# avr-clock.net
KiCad netlist of a schematic drawn in EAGLE
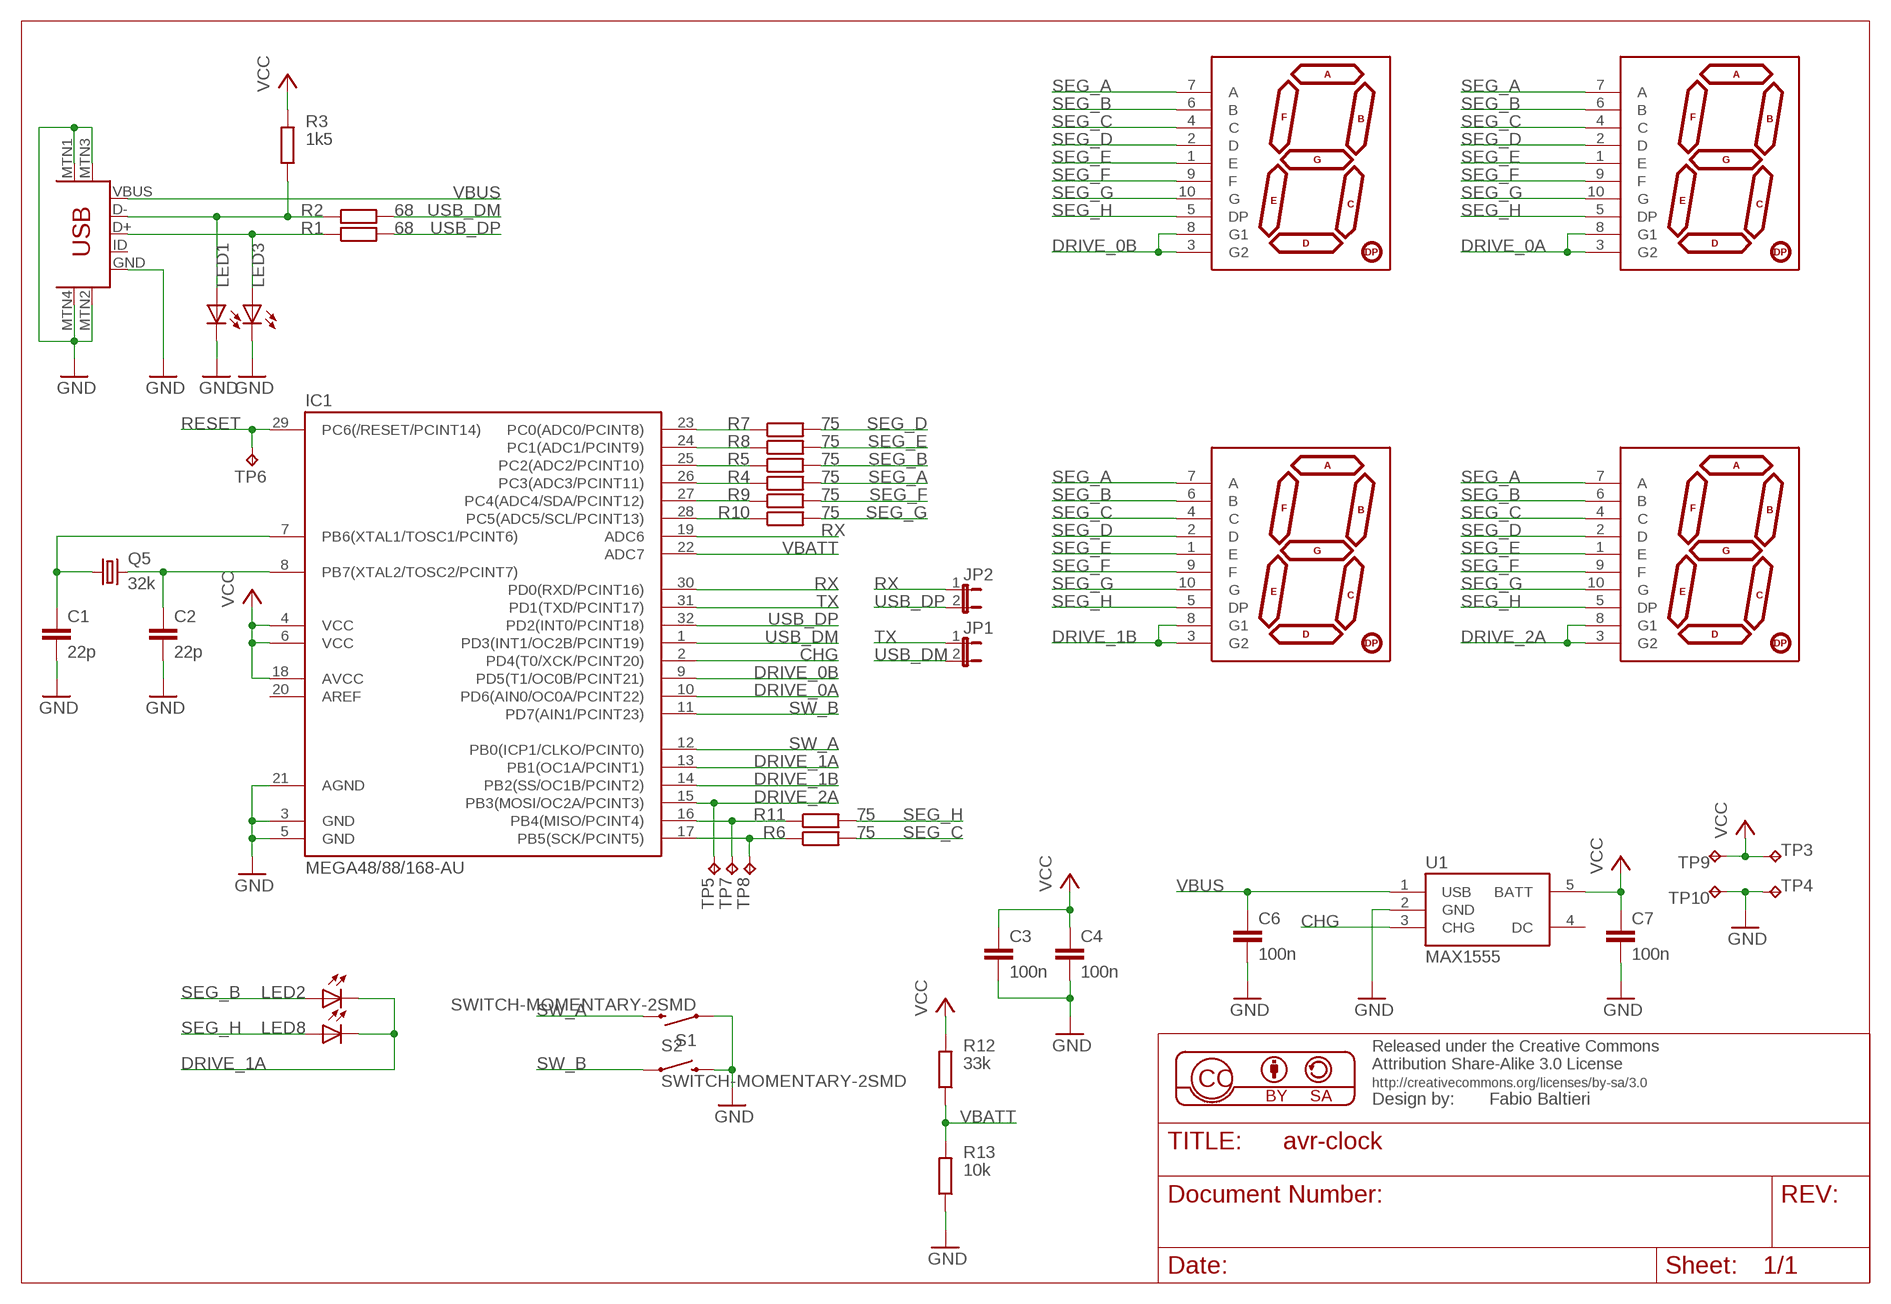
[diagram p0: schematic, sheet 1]

(export (version "E")
  (design (tool "Eeschema 10.0.6"))
  (components
    (comp (ref "C1")
      (value "22p")
      (footprint "eagle-import:C0805")
      (libsource (lib "eagle-import") (part "C-EUC0805"))
    )
    (comp (ref "C2")
      (value "22p")
      (footprint "eagle-import:C0805")
      (libsource (lib "eagle-import") (part "C-EUC0805"))
    )
    (comp (ref "C3")
      (value "100n")
      (footprint "eagle-import:C0805")
      (libsource (lib "eagle-import") (part "C-EUC0805"))
    )
    (comp (ref "C4")
      (value "100n")
      (footprint "eagle-import:C0805")
      (libsource (lib "eagle-import") (part "C-EUC0805"))
    )
    (comp (ref "C6")
      (value "100n")
      (footprint "eagle-import:C0805")
      (libsource (lib "eagle-import") (part "C-EUC0805"))
    )
    (comp (ref "C7")
      (value "100n")
      (footprint "eagle-import:C0805")
      (libsource (lib "eagle-import") (part "C-EUC0805"))
    )
    (comp (ref "IC1")
      (value "MEGA48/88/168-AU")
      (footprint "eagle-import:TQFP32-08")
      (libsource (lib "eagle-import") (part "MEGA48/88/168-AU"))
    )
    (comp (ref "JP1")
      (value "JUMPER-2SMD-NC")
      (footprint "eagle-import:SJ_2S")
      (libsource (lib "eagle-import") (part "JUMPER-2SMD-NC"))
    )
    (comp (ref "JP2")
      (value "JUMPER-2SMD-NC")
      (footprint "eagle-import:SJ_2S")
      (libsource (lib "eagle-import") (part "JUMPER-2SMD-NC"))
    )
    (comp (ref "LED1")
      (value "LEDCHIPLED_1206")
      (footprint "eagle-import:CHIPLED_1206")
      (libsource (lib "eagle-import") (part "LEDCHIPLED_1206"))
    )
    (comp (ref "LED2")
      (value "LEDCHIPLED_1206")
      (footprint "eagle-import:CHIPLED_1206")
      (libsource (lib "eagle-import") (part "LEDCHIPLED_1206"))
    )
    (comp (ref "LED3")
      (value "LEDCHIPLED_1206")
      (footprint "eagle-import:CHIPLED_1206")
      (libsource (lib "eagle-import") (part "LEDCHIPLED_1206"))
    )
    (comp (ref "LED8")
      (value "LEDCHIPLED_1206")
      (footprint "eagle-import:CHIPLED_1206")
      (libsource (lib "eagle-import") (part "LEDCHIPLED_1206"))
    )
    (comp (ref "Q5")
      (value "32k")
      (footprint "eagle-import:CTS406")
      (libsource (lib "eagle-import") (part "CRYSTALCTS406"))
    )
    (comp (ref "R1")
      (value "68")
      (footprint "eagle-import:R0603")
      (libsource (lib "eagle-import") (part "R-EU_R0603"))
    )
    (comp (ref "R2")
      (value "68")
      (footprint "eagle-import:R0603")
      (libsource (lib "eagle-import") (part "R-EU_R0603"))
    )
    (comp (ref "R3")
      (value "1k5")
      (footprint "eagle-import:R0603")
      (libsource (lib "eagle-import") (part "R-EU_R0603"))
    )
    (comp (ref "R4")
      (value "75")
      (footprint "eagle-import:R0603")
      (libsource (lib "eagle-import") (part "R-EU_R0603"))
    )
    (comp (ref "R5")
      (value "75")
      (footprint "eagle-import:R0603")
      (libsource (lib "eagle-import") (part "R-EU_R0603"))
    )
    (comp (ref "R6")
      (value "75")
      (footprint "eagle-import:R0603")
      (libsource (lib "eagle-import") (part "R-EU_R0603"))
    )
    (comp (ref "R7")
      (value "75")
      (footprint "eagle-import:R0603")
      (libsource (lib "eagle-import") (part "R-EU_R0603"))
    )
    (comp (ref "R8")
      (value "75")
      (footprint "eagle-import:R0603")
      (libsource (lib "eagle-import") (part "R-EU_R0603"))
    )
    (comp (ref "R9")
      (value "75")
      (footprint "eagle-import:R0603")
      (libsource (lib "eagle-import") (part "R-EU_R0603"))
    )
    (comp (ref "R10")
      (value "75")
      (footprint "eagle-import:R0603")
      (libsource (lib "eagle-import") (part "R-EU_R0603"))
    )
    (comp (ref "R11")
      (value "75")
      (footprint "eagle-import:R0603")
      (libsource (lib "eagle-import") (part "R-EU_R0603"))
    )
    (comp (ref "R12")
      (value "33k")
      (footprint "eagle-import:R0603")
      (libsource (lib "eagle-import") (part "R-EU_R0603"))
    )
    (comp (ref "R13")
      (value "10k")
      (footprint "eagle-import:R0603")
      (libsource (lib "eagle-import") (part "R-EU_R0603"))
    )
    (comp (ref "S1")
      (value "SWITCH-MOMENTARY-2SMD")
      (footprint "eagle-import:TACTILE_SWITCH_SMD")
      (libsource (lib "eagle-import") (part "SWITCH-MOMENTARY-2SMD"))
    )
    (comp (ref "S2")
      (value "SWITCH-MOMENTARY-2SMD")
      (footprint "eagle-import:TACTILE_SWITCH_SMD")
      (libsource (lib "eagle-import") (part "SWITCH-MOMENTARY-2SMD"))
    )
    (comp (ref "TP3")
      (value "TPB1,27")
      (footprint "eagle-import:B1,27")
      (libsource (lib "eagle-import") (part "TPB1,27"))
    )
    (comp (ref "TP4")
      (value "TPB1,27")
      (footprint "eagle-import:B1,27")
      (libsource (lib "eagle-import") (part "TPB1,27"))
    )
    (comp (ref "TP5")
      (value "TPTP08R")
      (footprint "eagle-import:TP08R")
      (libsource (lib "eagle-import") (part "TPTP08R"))
    )
    (comp (ref "TP6")
      (value "TPTP08R")
      (footprint "eagle-import:TP08R")
      (libsource (lib "eagle-import") (part "TPTP08R"))
    )
    (comp (ref "TP7")
      (value "TPTP08R")
      (footprint "eagle-import:TP08R")
      (libsource (lib "eagle-import") (part "TPTP08R"))
    )
    (comp (ref "TP8")
      (value "TPTP08R")
      (footprint "eagle-import:TP08R")
      (libsource (lib "eagle-import") (part "TPTP08R"))
    )
    (comp (ref "TP9")
      (value "TPTP08R")
      (footprint "eagle-import:TP08R")
      (libsource (lib "eagle-import") (part "TPTP08R"))
    )
    (comp (ref "TP10")
      (value "TPTP08R")
      (footprint "eagle-import:TP08R")
      (libsource (lib "eagle-import") (part "TPTP08R"))
    )
    (comp (ref "U$1")
      (value "7-SEGMENT-DISPLAY-1\"-RED")
      (footprint "eagle-import:7-SEGMENT-SMD")
      (libsource (lib "eagle-import") (part "7-SEGMENT-DISPLAY-1{dblquote}-RED"))
    )
    (comp (ref "U$2")
      (value "USB-MINIB-5PIN")
      (footprint "eagle-import:USB-MINIB")
      (libsource (lib "eagle-import") (part "USB-MINIB-5PIN"))
    )
    (comp (ref "U$3")
      (value "7-SEGMENT-DISPLAY-1\"-RED")
      (footprint "eagle-import:7-SEGMENT-SMD")
      (libsource (lib "eagle-import") (part "7-SEGMENT-DISPLAY-1{dblquote}-RED"))
    )
    (comp (ref "U$4")
      (value "7-SEGMENT-DISPLAY-1\"-RED")
      (footprint "eagle-import:7-SEGMENT-SMD")
      (libsource (lib "eagle-import") (part "7-SEGMENT-DISPLAY-1{dblquote}-RED"))
    )
    (comp (ref "U$5")
      (value "7-SEGMENT-DISPLAY-1\"-RED")
      (footprint "eagle-import:7-SEGMENT-SMD")
      (libsource (lib "eagle-import") (part "7-SEGMENT-DISPLAY-1{dblquote}-RED"))
    )
    (comp (ref "U1")
      (value "MAX1555")
      (footprint "eagle-import:SOT23-5")
      (libsource (lib "eagle-import") (part "MAX1555"))
    )
  )
  (nets
    (net (code "1") (name "/CHG") (class "Default")
      (node (ref "IC1") (pin "2") (pinfunction "PD4(T0/XCK/PCINT20)_2") (pintype "bidirectional"))
      (node (ref "U1") (pin "3") (pinfunction "CHG_3") (pintype "bidirectional"))
    )
    (net (code "2") (name "/DRIVE_0A") (class "Default")
      (node (ref "IC1") (pin "10") (pinfunction "PD6(AIN0/OC0A/PCINT22)_10") (pintype "bidirectional"))
      (node (ref "U$3") (pin "3") (pinfunction "G2_3") (pintype "bidirectional"))
      (node (ref "U$3") (pin "8") (pinfunction "G1_8") (pintype "bidirectional"))
    )
    (net (code "3") (name "/DRIVE_0B") (class "Default")
      (node (ref "IC1") (pin "9") (pinfunction "PD5(T1/OC0B/PCINT21)_9") (pintype "bidirectional"))
      (node (ref "U$1") (pin "3") (pinfunction "G2_3") (pintype "bidirectional"))
      (node (ref "U$1") (pin "8") (pinfunction "G1_8") (pintype "bidirectional"))
    )
    (net (code "4") (name "/DRIVE_1A") (class "Default")
      (node (ref "IC1") (pin "13") (pinfunction "PB1(OC1A/PCINT1)_13") (pintype "bidirectional"))
      (node (ref "LED2") (pin "C") (pinfunction "C_C") (pintype "passive"))
      (node (ref "LED8") (pin "C") (pinfunction "C_C") (pintype "passive"))
    )
    (net (code "5") (name "/DRIVE_1B") (class "Default")
      (node (ref "IC1") (pin "14") (pinfunction "PB2(SS/OC1B/PCINT2)_14") (pintype "bidirectional"))
      (node (ref "U$4") (pin "3") (pinfunction "G2_3") (pintype "bidirectional"))
      (node (ref "U$4") (pin "8") (pinfunction "G1_8") (pintype "bidirectional"))
    )
    (net (code "6") (name "/DRIVE_2A") (class "Default")
      (node (ref "IC1") (pin "15") (pinfunction "PB3(MOSI/OC2A/PCINT3)_15") (pintype "bidirectional"))
      (node (ref "TP5") (pin "TP") (pinfunction "TP_TP") (pintype "input"))
      (node (ref "U$5") (pin "3") (pinfunction "G2_3") (pintype "bidirectional"))
      (node (ref "U$5") (pin "8") (pinfunction "G1_8") (pintype "bidirectional"))
    )
    (net (code "7") (name "/RESET") (class "Default")
      (node (ref "IC1") (pin "29") (pinfunction "PC6(/RESET/PCINT14)_29") (pintype "bidirectional"))
      (node (ref "TP6") (pin "TP") (pinfunction "TP_TP") (pintype "input"))
    )
    (net (code "8") (name "/RX") (class "Default")
      (node (ref "IC1") (pin "19") (pinfunction "ADC6_19") (pintype "passive"))
      (node (ref "IC1") (pin "30") (pinfunction "PD0(RXD/PCINT16)_30") (pintype "bidirectional"))
      (node (ref "JP2") (pin "1") (pinfunction "1_1") (pintype "passive"))
    )
    (net (code "9") (name "/SEG_A") (class "Default")
      (node (ref "R4") (pin "2") (pinfunction "2_2") (pintype "passive"))
      (node (ref "U$1") (pin "7") (pinfunction "A_7") (pintype "bidirectional"))
      (node (ref "U$3") (pin "7") (pinfunction "A_7") (pintype "bidirectional"))
      (node (ref "U$4") (pin "7") (pinfunction "A_7") (pintype "bidirectional"))
      (node (ref "U$5") (pin "7") (pinfunction "A_7") (pintype "bidirectional"))
    )
    (net (code "10") (name "/SEG_B") (class "Default")
      (node (ref "LED2") (pin "A") (pinfunction "A_A") (pintype "passive"))
      (node (ref "R5") (pin "2") (pinfunction "2_2") (pintype "passive"))
      (node (ref "U$1") (pin "6") (pinfunction "B_6") (pintype "bidirectional"))
      (node (ref "U$3") (pin "6") (pinfunction "B_6") (pintype "bidirectional"))
      (node (ref "U$4") (pin "6") (pinfunction "B_6") (pintype "bidirectional"))
      (node (ref "U$5") (pin "6") (pinfunction "B_6") (pintype "bidirectional"))
    )
    (net (code "11") (name "/SEG_C") (class "Default")
      (node (ref "R6") (pin "2") (pinfunction "2_2") (pintype "passive"))
      (node (ref "U$1") (pin "4") (pinfunction "C_4") (pintype "bidirectional"))
      (node (ref "U$3") (pin "4") (pinfunction "C_4") (pintype "bidirectional"))
      (node (ref "U$4") (pin "4") (pinfunction "C_4") (pintype "bidirectional"))
      (node (ref "U$5") (pin "4") (pinfunction "C_4") (pintype "bidirectional"))
    )
    (net (code "12") (name "/SEG_D") (class "Default")
      (node (ref "R7") (pin "2") (pinfunction "2_2") (pintype "passive"))
      (node (ref "U$1") (pin "2") (pinfunction "D_2") (pintype "bidirectional"))
      (node (ref "U$3") (pin "2") (pinfunction "D_2") (pintype "bidirectional"))
      (node (ref "U$4") (pin "2") (pinfunction "D_2") (pintype "bidirectional"))
      (node (ref "U$5") (pin "2") (pinfunction "D_2") (pintype "bidirectional"))
    )
    (net (code "13") (name "/SEG_E") (class "Default")
      (node (ref "R8") (pin "2") (pinfunction "2_2") (pintype "passive"))
      (node (ref "U$1") (pin "1") (pinfunction "E_1") (pintype "bidirectional"))
      (node (ref "U$3") (pin "1") (pinfunction "E_1") (pintype "bidirectional"))
      (node (ref "U$4") (pin "1") (pinfunction "E_1") (pintype "bidirectional"))
      (node (ref "U$5") (pin "1") (pinfunction "E_1") (pintype "bidirectional"))
    )
    (net (code "14") (name "/SEG_F") (class "Default")
      (node (ref "R9") (pin "2") (pinfunction "2_2") (pintype "passive"))
      (node (ref "U$1") (pin "9") (pinfunction "F_9") (pintype "bidirectional"))
      (node (ref "U$3") (pin "9") (pinfunction "F_9") (pintype "bidirectional"))
      (node (ref "U$4") (pin "9") (pinfunction "F_9") (pintype "bidirectional"))
      (node (ref "U$5") (pin "9") (pinfunction "F_9") (pintype "bidirectional"))
    )
    (net (code "15") (name "/SEG_G") (class "Default")
      (node (ref "R10") (pin "2") (pinfunction "2_2") (pintype "passive"))
      (node (ref "U$1") (pin "10") (pinfunction "G_10") (pintype "bidirectional"))
      (node (ref "U$3") (pin "10") (pinfunction "G_10") (pintype "bidirectional"))
      (node (ref "U$4") (pin "10") (pinfunction "G_10") (pintype "bidirectional"))
      (node (ref "U$5") (pin "10") (pinfunction "G_10") (pintype "bidirectional"))
    )
    (net (code "16") (name "/SEG_H") (class "Default")
      (node (ref "LED8") (pin "A") (pinfunction "A_A") (pintype "passive"))
      (node (ref "R11") (pin "2") (pinfunction "2_2") (pintype "passive"))
      (node (ref "U$1") (pin "5") (pinfunction "DP_5") (pintype "bidirectional"))
      (node (ref "U$3") (pin "5") (pinfunction "DP_5") (pintype "bidirectional"))
      (node (ref "U$4") (pin "5") (pinfunction "DP_5") (pintype "bidirectional"))
      (node (ref "U$5") (pin "5") (pinfunction "DP_5") (pintype "bidirectional"))
    )
    (net (code "17") (name "/SW_A") (class "Default")
      (node (ref "IC1") (pin "12") (pinfunction "PB0(ICP1/CLKO/PCINT0)_12") (pintype "bidirectional"))
      (node (ref "S1") (pin "3") (pinfunction "2_3") (pintype "passive"))
    )
    (net (code "18") (name "/SW_B") (class "Default")
      (node (ref "IC1") (pin "11") (pinfunction "PD7(AIN1/PCINT23)_11") (pintype "bidirectional"))
      (node (ref "S2") (pin "1") (pinfunction "1_1") (pintype "passive"))
    )
    (net (code "19") (name "/TX") (class "Default")
      (node (ref "IC1") (pin "31") (pinfunction "PD1(TXD/PCINT17)_31") (pintype "bidirectional"))
      (node (ref "JP1") (pin "1") (pinfunction "1_1") (pintype "passive"))
    )
    (net (code "20") (name "/USB_DM") (class "Default")
      (node (ref "IC1") (pin "1") (pinfunction "PD3(INT1/OC2B/PCINT19)_1") (pintype "bidirectional"))
      (node (ref "JP1") (pin "2") (pinfunction "2_2") (pintype "passive"))
      (node (ref "R2") (pin "2") (pinfunction "2_2") (pintype "passive"))
    )
    (net (code "21") (name "/USB_DP") (class "Default")
      (node (ref "IC1") (pin "32") (pinfunction "PD2(INT0/PCINT18)_32") (pintype "bidirectional"))
      (node (ref "JP2") (pin "2") (pinfunction "2_2") (pintype "passive"))
      (node (ref "R1") (pin "2") (pinfunction "2_2") (pintype "passive"))
    )
    (net (code "22") (name "/VBATT") (class "Default")
      (node (ref "IC1") (pin "22") (pinfunction "ADC7_22") (pintype "passive"))
      (node (ref "R12") (pin "1") (pinfunction "1_1") (pintype "passive"))
      (node (ref "R13") (pin "2") (pinfunction "2_2") (pintype "passive"))
    )
    (net (code "23") (name "/VBUS") (class "Default")
      (node (ref "C6") (pin "1") (pinfunction "1_1") (pintype "passive"))
      (node (ref "U$2") (pin "VBUS") (pinfunction "VBUS_VBUS") (pintype "bidirectional"))
      (node (ref "U1") (pin "1") (pinfunction "USB_1") (pintype "bidirectional"))
    )
    (net (code "24") (name "GND") (class "Default")
      (node (ref "C1") (pin "2") (pinfunction "2_2") (pintype "passive"))
      (node (ref "C2") (pin "2") (pinfunction "2_2") (pintype "passive"))
      (node (ref "C3") (pin "2") (pinfunction "2_2") (pintype "passive"))
      (node (ref "C4") (pin "2") (pinfunction "2_2") (pintype "passive"))
      (node (ref "C6") (pin "2") (pinfunction "2_2") (pintype "passive"))
      (node (ref "C7") (pin "2") (pinfunction "2_2") (pintype "passive"))
      (node (ref "IC1") (pin "21") (pinfunction "AGND_21") (pintype "power_in"))
      (node (ref "IC1") (pin "3") (pinfunction "GND_3") (pintype "power_in"))
      (node (ref "IC1") (pin "5") (pinfunction "GND_5") (pintype "power_in"))
      (node (ref "LED1") (pin "C") (pinfunction "C_C") (pintype "passive"))
      (node (ref "LED3") (pin "C") (pinfunction "C_C") (pintype "passive"))
      (node (ref "R13") (pin "1") (pinfunction "1_1") (pintype "passive"))
      (node (ref "S1") (pin "1") (pinfunction "1_1") (pintype "passive"))
      (node (ref "S2") (pin "3") (pinfunction "2_3") (pintype "passive"))
      (node (ref "TP10") (pin "TP") (pinfunction "TP_TP") (pintype "input"))
      (node (ref "TP4") (pin "TP") (pinfunction "TP_TP") (pintype "input"))
      (node (ref "U$2") (pin "GND") (pinfunction "GND_GND") (pintype "bidirectional"))
      (node (ref "U$2") (pin "MTN1") (pinfunction "MTN2_MTN1") (pintype "bidirectional"))
      (node (ref "U$2") (pin "MTN2") (pinfunction "MTN3_MTN2") (pintype "bidirectional"))
      (node (ref "U$2") (pin "MTN3") (pinfunction "MTN1_MTN3") (pintype "bidirectional"))
      (node (ref "U$2") (pin "MTN4") (pinfunction "MTN4_MTN4") (pintype "bidirectional"))
      (node (ref "U1") (pin "2") (pinfunction "GND_2") (pintype "bidirectional"))
    )
    (net (code "25") (name "Net-(IC1-PB4(MISO{slash}PCINT4))") (class "Default")
      (node (ref "IC1") (pin "16") (pinfunction "PB4(MISO/PCINT4)_16") (pintype "bidirectional"))
      (node (ref "R11") (pin "1") (pinfunction "1_1") (pintype "passive"))
      (node (ref "TP7") (pin "TP") (pinfunction "TP_TP") (pintype "input"))
    )
    (net (code "26") (name "Net-(IC1-PB5(SCK{slash}PCINT5))") (class "Default")
      (node (ref "IC1") (pin "17") (pinfunction "PB5(SCK/PCINT5)_17") (pintype "bidirectional"))
      (node (ref "R6") (pin "1") (pinfunction "1_1") (pintype "passive"))
      (node (ref "TP8") (pin "TP") (pinfunction "TP_TP") (pintype "input"))
    )
    (net (code "27") (name "Net-(IC1-PB6(XTAL1{slash}TOSC1{slash}PCINT6))") (class "Default")
      (node (ref "C1") (pin "1") (pinfunction "1_1") (pintype "passive"))
      (node (ref "IC1") (pin "7") (pinfunction "PB6(XTAL1/TOSC1/PCINT6)_7") (pintype "bidirectional"))
      (node (ref "Q5") (pin "1") (pinfunction "1_1") (pintype "passive"))
    )
    (net (code "28") (name "Net-(IC1-PB7(XTAL2{slash}TOSC2{slash}PCINT7))") (class "Default")
      (node (ref "C2") (pin "1") (pinfunction "1_1") (pintype "passive"))
      (node (ref "IC1") (pin "8") (pinfunction "PB7(XTAL2/TOSC2/PCINT7)_8") (pintype "bidirectional"))
      (node (ref "Q5") (pin "3") (pinfunction "2_3") (pintype "passive"))
    )
    (net (code "29") (name "Net-(IC1-PC0(ADC0{slash}PCINT8))") (class "Default")
      (node (ref "IC1") (pin "23") (pinfunction "PC0(ADC0/PCINT8)_23") (pintype "bidirectional"))
      (node (ref "R7") (pin "1") (pinfunction "1_1") (pintype "passive"))
    )
    (net (code "30") (name "Net-(IC1-PC1(ADC1{slash}PCINT9))") (class "Default")
      (node (ref "IC1") (pin "24") (pinfunction "PC1(ADC1/PCINT9)_24") (pintype "bidirectional"))
      (node (ref "R8") (pin "1") (pinfunction "1_1") (pintype "passive"))
    )
    (net (code "31") (name "Net-(IC1-PC2(ADC2{slash}PCINT10))") (class "Default")
      (node (ref "IC1") (pin "25") (pinfunction "PC2(ADC2/PCINT10)_25") (pintype "bidirectional"))
      (node (ref "R5") (pin "1") (pinfunction "1_1") (pintype "passive"))
    )
    (net (code "32") (name "Net-(IC1-PC3(ADC3{slash}PCINT11))") (class "Default")
      (node (ref "IC1") (pin "26") (pinfunction "PC3(ADC3/PCINT11)_26") (pintype "bidirectional"))
      (node (ref "R4") (pin "1") (pinfunction "1_1") (pintype "passive"))
    )
    (net (code "33") (name "Net-(IC1-PC4(ADC4{slash}SDA{slash}PCINT12))") (class "Default")
      (node (ref "IC1") (pin "27") (pinfunction "PC4(ADC4/SDA/PCINT12)_27") (pintype "bidirectional"))
      (node (ref "R9") (pin "1") (pinfunction "1_1") (pintype "passive"))
    )
    (net (code "34") (name "Net-(IC1-PC5(ADC5{slash}SCL{slash}PCINT13))") (class "Default")
      (node (ref "IC1") (pin "28") (pinfunction "PC5(ADC5/SCL/PCINT13)_28") (pintype "bidirectional"))
      (node (ref "R10") (pin "1") (pinfunction "1_1") (pintype "passive"))
    )
    (net (code "35") (name "Net-(LED1-PadA)") (class "Default")
      (node (ref "LED1") (pin "A") (pinfunction "A_A") (pintype "passive"))
      (node (ref "R2") (pin "1") (pinfunction "1_1") (pintype "passive"))
      (node (ref "R3") (pin "1") (pinfunction "1_1") (pintype "passive"))
      (node (ref "U$2") (pin "D-") (pinfunction "D-_D-") (pintype "bidirectional"))
    )
    (net (code "36") (name "Net-(LED3-PadA)") (class "Default")
      (node (ref "LED3") (pin "A") (pinfunction "A_A") (pintype "passive"))
      (node (ref "R1") (pin "1") (pinfunction "1_1") (pintype "passive"))
      (node (ref "U$2") (pin "D+") (pinfunction "D+_D+") (pintype "bidirectional"))
    )
    (net (code "37") (name "VCC") (class "Default")
      (node (ref "C3") (pin "1") (pinfunction "1_1") (pintype "passive"))
      (node (ref "C4") (pin "1") (pinfunction "1_1") (pintype "passive"))
      (node (ref "C7") (pin "1") (pinfunction "1_1") (pintype "passive"))
      (node (ref "IC1") (pin "18") (pinfunction "AVCC_18") (pintype "passive"))
      (node (ref "IC1") (pin "4") (pinfunction "VCC_4") (pintype "power_in"))
      (node (ref "IC1") (pin "6") (pinfunction "VCC_6") (pintype "power_in"))
      (node (ref "R12") (pin "2") (pinfunction "2_2") (pintype "passive"))
      (node (ref "R3") (pin "2") (pinfunction "2_2") (pintype "passive"))
      (node (ref "TP3") (pin "TP") (pinfunction "TP_TP") (pintype "input"))
      (node (ref "TP9") (pin "TP") (pinfunction "TP_TP") (pintype "input"))
      (node (ref "U1") (pin "5") (pinfunction "BATT_5") (pintype "bidirectional"))
    )
    (net (code "38") (name "unconnected-(IC1-AREF-Pad20)") (class "Default")
      (node (ref "IC1") (pin "20") (pinfunction "AREF_20") (pintype "passive"))
    )
    (net (code "39") (name "unconnected-(U$2-PadID)") (class "Default")
      (node (ref "U$2") (pin "ID") (pinfunction "ID_ID") (pintype "bidirectional"))
    )
    (net (code "40") (name "unconnected-(U1-DC-Pad4)") (class "Default")
      (node (ref "U1") (pin "4") (pinfunction "DC_4") (pintype "bidirectional"))
    )
  )
)
